# PULSE.net
KiCad netlist of a schematic drawn in Altium Designer
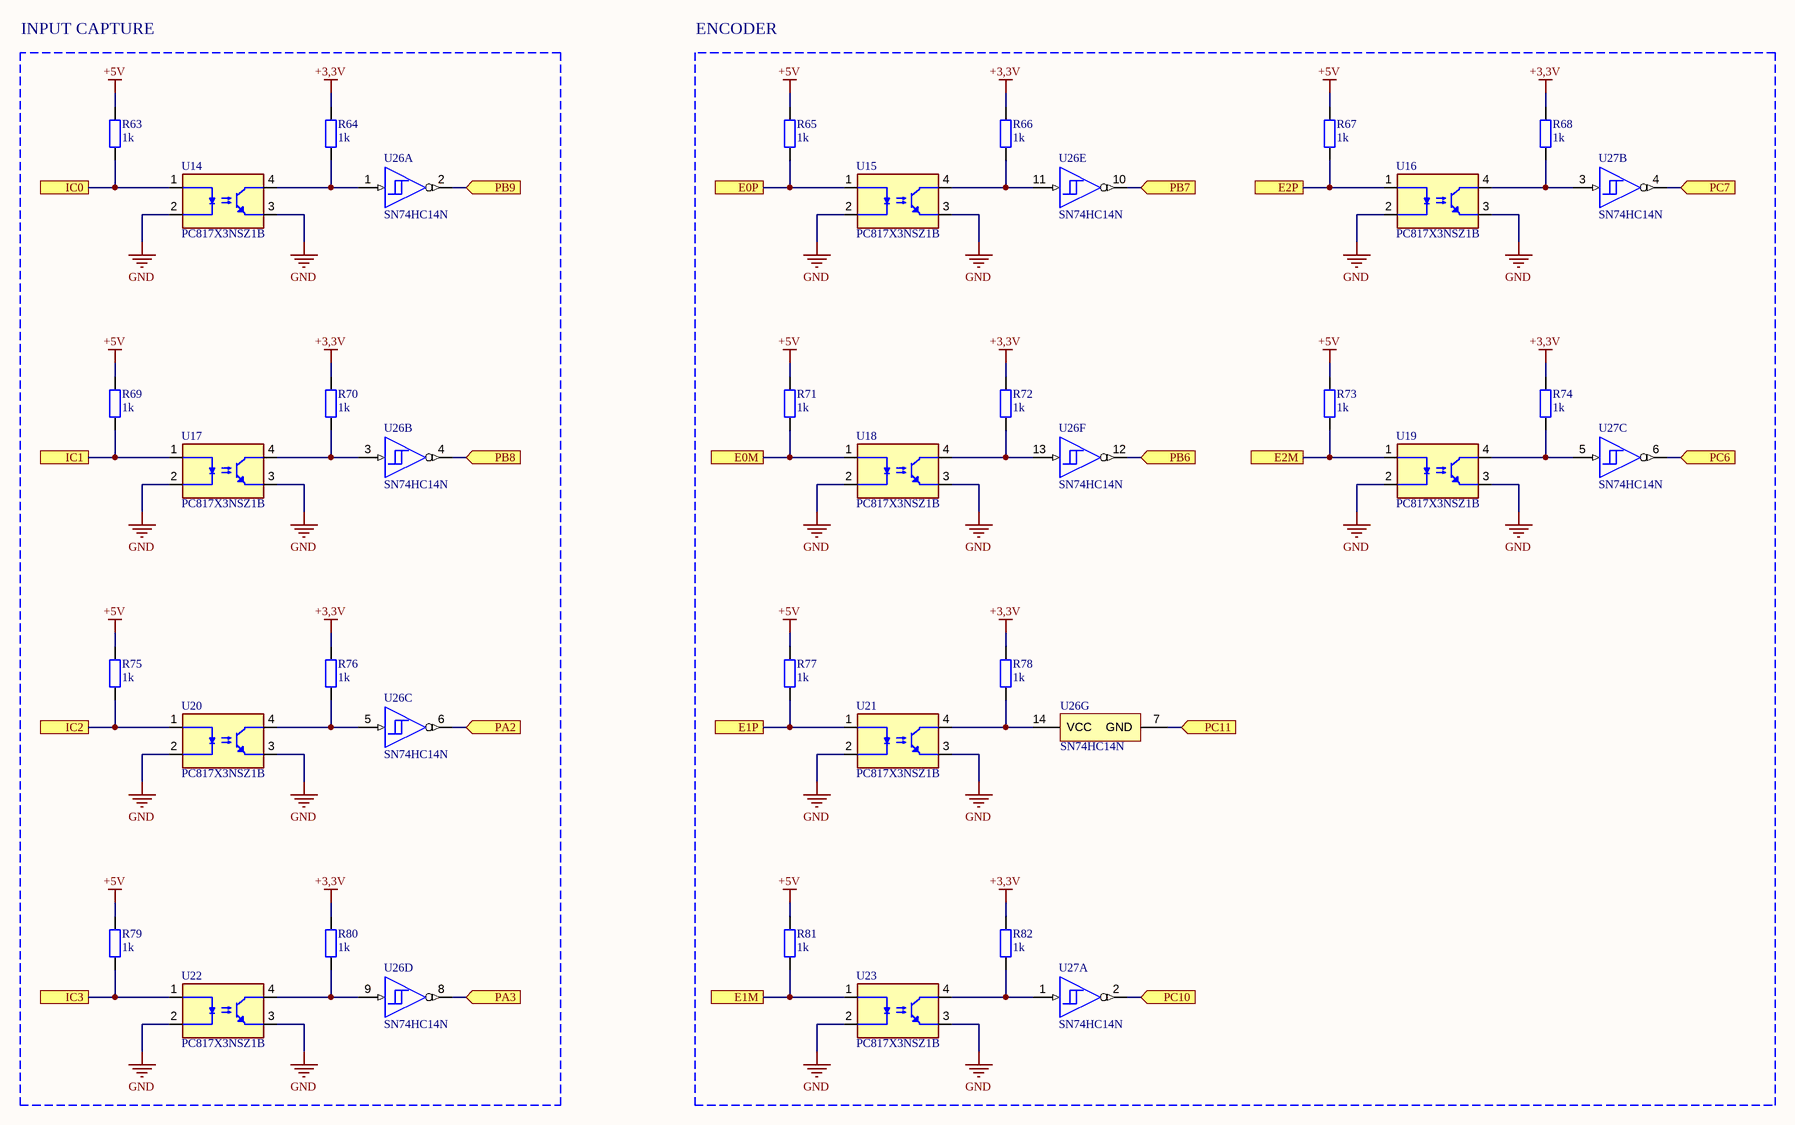
[diagram p0: PULSE.SchDoc]

(export (version "E")
  (design (tool "Eeschema 10.0.6"))
  (components
    (comp (ref "R63")
      (value "1k")
      (footprint "tro smd 0603")
      (description "RES")
      (libsource (lib "AUSB") (part "Tro 0603 1% 10k"))
    )
    (comp (ref "R64")
      (value "1k")
      (footprint "tro smd 0603")
      (description "RES")
      (libsource (lib "AUSB") (part "Tro 0603 1% 10k"))
    )
    (comp (ref "R65")
      (value "1k")
      (footprint "tro smd 0603")
      (description "RES")
      (libsource (lib "AUSB") (part "Tro 0603 1% 10k"))
    )
    (comp (ref "R66")
      (value "1k")
      (footprint "tro smd 0603")
      (description "RES")
      (libsource (lib "AUSB") (part "Tro 0603 1% 10k"))
    )
    (comp (ref "R67")
      (value "1k")
      (footprint "tro smd 0603")
      (description "RES")
      (libsource (lib "AUSB") (part "Tro 0603 1% 10k"))
    )
    (comp (ref "R68")
      (value "1k")
      (footprint "tro smd 0603")
      (description "RES")
      (libsource (lib "AUSB") (part "Tro 0603 1% 10k"))
    )
    (comp (ref "R69")
      (value "1k")
      (footprint "tro smd 0603")
      (description "RES")
      (libsource (lib "AUSB") (part "Tro 0603 1% 10k"))
    )
    (comp (ref "R70")
      (value "1k")
      (footprint "tro smd 0603")
      (description "RES")
      (libsource (lib "AUSB") (part "Tro 0603 1% 10k"))
    )
    (comp (ref "R71")
      (value "1k")
      (footprint "tro smd 0603")
      (description "RES")
      (libsource (lib "AUSB") (part "Tro 0603 1% 10k"))
    )
    (comp (ref "R72")
      (value "1k")
      (footprint "tro smd 0603")
      (description "RES")
      (libsource (lib "AUSB") (part "Tro 0603 1% 10k"))
    )
    (comp (ref "R73")
      (value "1k")
      (footprint "tro smd 0603")
      (description "RES")
      (libsource (lib "AUSB") (part "Tro 0603 1% 10k"))
    )
    (comp (ref "R74")
      (value "1k")
      (footprint "tro smd 0603")
      (description "RES")
      (libsource (lib "AUSB") (part "Tro 0603 1% 10k"))
    )
    (comp (ref "R75")
      (value "1k")
      (footprint "tro smd 0603")
      (description "RES")
      (libsource (lib "AUSB") (part "Tro 0603 1% 10k"))
    )
    (comp (ref "R76")
      (value "1k")
      (footprint "tro smd 0603")
      (description "RES")
      (libsource (lib "AUSB") (part "Tro 0603 1% 10k"))
    )
    (comp (ref "R77")
      (value "1k")
      (footprint "tro smd 0603")
      (description "RES")
      (libsource (lib "AUSB") (part "Tro 0603 1% 10k"))
    )
    (comp (ref "R78")
      (value "1k")
      (footprint "tro smd 0603")
      (description "RES")
      (libsource (lib "AUSB") (part "Tro 0603 1% 10k"))
    )
    (comp (ref "R79")
      (value "1k")
      (footprint "tro smd 0603")
      (description "RES")
      (libsource (lib "AUSB") (part "Tro 0603 1% 10k"))
    )
    (comp (ref "R80")
      (value "1k")
      (footprint "tro smd 0603")
      (description "RES")
      (libsource (lib "AUSB") (part "Tro 0603 1% 10k"))
    )
    (comp (ref "R81")
      (value "1k")
      (footprint "tro smd 0603")
      (description "RES")
      (libsource (lib "AUSB") (part "Tro 0603 1% 10k"))
    )
    (comp (ref "R82")
      (value "1k")
      (footprint "tro smd 0603")
      (description "RES")
      (libsource (lib "AUSB") (part "Tro 0603 1% 10k"))
    )
    (comp (ref "U14")
      (value "PC817X3NSZ1B")
      (footprint "DIP762W50P254L495H455Q4")
      (description "Optoisolator Transistor Output - 1 Channel 4-DIP")
      (fields (field (name "MF") "Sharp Microelectronics"))
      (libsource (lib "PC817X3NSZ1B") (part "PC817X3NSZ1B"))
    )
    (comp (ref "U15")
      (value "PC817X3NSZ1B")
      (footprint "DIP762W50P254L495H455Q4")
      (description "Optoisolator Transistor Output - 1 Channel 4-DIP")
      (fields (field (name "MF") "Sharp Microelectronics"))
      (libsource (lib "PC817X3NSZ1B") (part "PC817X3NSZ1B"))
    )
    (comp (ref "U16")
      (value "PC817X3NSZ1B")
      (footprint "DIP762W50P254L495H455Q4")
      (description "Optoisolator Transistor Output - 1 Channel 4-DIP")
      (fields (field (name "MF") "Sharp Microelectronics"))
      (libsource (lib "PC817X3NSZ1B") (part "PC817X3NSZ1B"))
    )
    (comp (ref "U17")
      (value "PC817X3NSZ1B")
      (footprint "DIP762W50P254L495H455Q4")
      (description "Optoisolator Transistor Output - 1 Channel 4-DIP")
      (fields (field (name "MF") "Sharp Microelectronics"))
      (libsource (lib "PC817X3NSZ1B") (part "PC817X3NSZ1B"))
    )
    (comp (ref "U18")
      (value "PC817X3NSZ1B")
      (footprint "DIP762W50P254L495H455Q4")
      (description "Optoisolator Transistor Output - 1 Channel 4-DIP")
      (fields (field (name "MF") "Sharp Microelectronics"))
      (libsource (lib "PC817X3NSZ1B") (part "PC817X3NSZ1B"))
    )
    (comp (ref "U19")
      (value "PC817X3NSZ1B")
      (footprint "DIP762W50P254L495H455Q4")
      (description "Optoisolator Transistor Output - 1 Channel 4-DIP")
      (fields (field (name "MF") "Sharp Microelectronics"))
      (libsource (lib "PC817X3NSZ1B") (part "PC817X3NSZ1B"))
    )
    (comp (ref "U20")
      (value "PC817X3NSZ1B")
      (footprint "DIP762W50P254L495H455Q4")
      (description "Optoisolator Transistor Output - 1 Channel 4-DIP")
      (fields (field (name "MF") "Sharp Microelectronics"))
      (libsource (lib "PC817X3NSZ1B") (part "PC817X3NSZ1B"))
    )
    (comp (ref "U21")
      (value "PC817X3NSZ1B")
      (footprint "DIP762W50P254L495H455Q4")
      (description "Optoisolator Transistor Output - 1 Channel 4-DIP")
      (fields (field (name "MF") "Sharp Microelectronics"))
      (libsource (lib "PC817X3NSZ1B") (part "PC817X3NSZ1B"))
    )
    (comp (ref "U22")
      (value "PC817X3NSZ1B")
      (footprint "DIP762W50P254L495H455Q4")
      (description "Optoisolator Transistor Output - 1 Channel 4-DIP")
      (fields (field (name "MF") "Sharp Microelectronics"))
      (libsource (lib "PC817X3NSZ1B") (part "PC817X3NSZ1B"))
    )
    (comp (ref "U23")
      (value "PC817X3NSZ1B")
      (footprint "DIP762W50P254L495H455Q4")
      (description "Optoisolator Transistor Output - 1 Channel 4-DIP")
      (fields (field (name "MF") "Sharp Microelectronics"))
      (libsource (lib "PC817X3NSZ1B") (part "PC817X3NSZ1B"))
    )
    (comp (ref "U26")
      (value "SN74HC14N")
      (footprint "N0014A")
      (description "Hex Schmitt-Trigger Inverters, N0014A, TUBE")
      (fields
        (field (name "MANUFACTURER") "Texas Instruments")
        (field (name "GENERIC PART NUMBER") "SN74HC14")
      )
      (libsource (lib "SN74HC14N") (part "CMP-1615-00889-3"))
    )
    (comp (ref "U27")
      (value "SN74HC14N")
      (footprint "N0014A")
      (description "Hex Schmitt-Trigger Inverters, N0014A, TUBE")
      (fields
        (field (name "MANUFACTURER") "Texas Instruments")
        (field (name "GENERIC PART NUMBER") "SN74HC14")
      )
      (libsource (lib "SN74HC14N") (part "CMP-1615-00889-3"))
    )
  )
  (nets
    (net (code "1") (name "+3,3V") (class "Default")
      (node (ref "R64") (pin "2") (pinfunction "2_2") (pintype "passive"))
      (node (ref "R66") (pin "2") (pinfunction "2_2") (pintype "passive"))
      (node (ref "R68") (pin "2") (pinfunction "2_2") (pintype "passive"))
      (node (ref "R70") (pin "2") (pinfunction "2_2") (pintype "passive"))
      (node (ref "R72") (pin "2") (pinfunction "2_2") (pintype "passive"))
      (node (ref "R74") (pin "2") (pinfunction "2_2") (pintype "passive"))
      (node (ref "R76") (pin "2") (pinfunction "2_2") (pintype "passive"))
      (node (ref "R78") (pin "2") (pinfunction "2_2") (pintype "passive"))
      (node (ref "R80") (pin "2") (pinfunction "2_2") (pintype "passive"))
      (node (ref "R82") (pin "2") (pinfunction "2_2") (pintype "passive"))
    )
    (net (code "2") (name "+5V") (class "Default")
      (node (ref "R63") (pin "2") (pinfunction "2_2") (pintype "passive"))
      (node (ref "R65") (pin "2") (pinfunction "2_2") (pintype "passive"))
      (node (ref "R67") (pin "2") (pinfunction "2_2") (pintype "passive"))
      (node (ref "R69") (pin "2") (pinfunction "2_2") (pintype "passive"))
      (node (ref "R71") (pin "2") (pinfunction "2_2") (pintype "passive"))
      (node (ref "R73") (pin "2") (pinfunction "2_2") (pintype "passive"))
      (node (ref "R75") (pin "2") (pinfunction "2_2") (pintype "passive"))
      (node (ref "R77") (pin "2") (pinfunction "2_2") (pintype "passive"))
      (node (ref "R79") (pin "2") (pinfunction "2_2") (pintype "passive"))
      (node (ref "R81") (pin "2") (pinfunction "2_2") (pintype "passive"))
    )
    (net (code "3") (name "/E0M") (class "Default")
      (node (ref "R71") (pin "1") (pinfunction "1_1") (pintype "passive"))
      (node (ref "U18") (pin "1") (pinfunction "ANODE_1") (pintype "passive"))
    )
    (net (code "4") (name "/E0P") (class "Default")
      (node (ref "R65") (pin "1") (pinfunction "1_1") (pintype "passive"))
      (node (ref "U15") (pin "1") (pinfunction "ANODE_1") (pintype "passive"))
    )
    (net (code "5") (name "/E1M") (class "Default")
      (node (ref "R81") (pin "1") (pinfunction "1_1") (pintype "passive"))
      (node (ref "U23") (pin "1") (pinfunction "ANODE_1") (pintype "passive"))
    )
    (net (code "6") (name "/E1P") (class "Default")
      (node (ref "R77") (pin "1") (pinfunction "1_1") (pintype "passive"))
      (node (ref "U21") (pin "1") (pinfunction "ANODE_1") (pintype "passive"))
    )
    (net (code "7") (name "/E2M") (class "Default")
      (node (ref "R73") (pin "1") (pinfunction "1_1") (pintype "passive"))
      (node (ref "U19") (pin "1") (pinfunction "ANODE_1") (pintype "passive"))
    )
    (net (code "8") (name "/E2P") (class "Default")
      (node (ref "R67") (pin "1") (pinfunction "1_1") (pintype "passive"))
      (node (ref "U16") (pin "1") (pinfunction "ANODE_1") (pintype "passive"))
    )
    (net (code "9") (name "/IC0") (class "Default")
      (node (ref "R63") (pin "1") (pinfunction "1_1") (pintype "passive"))
      (node (ref "U14") (pin "1") (pinfunction "ANODE_1") (pintype "passive"))
    )
    (net (code "10") (name "/IC1") (class "Default")
      (node (ref "R69") (pin "1") (pinfunction "1_1") (pintype "passive"))
      (node (ref "U17") (pin "1") (pinfunction "ANODE_1") (pintype "passive"))
    )
    (net (code "11") (name "/IC2") (class "Default")
      (node (ref "R75") (pin "1") (pinfunction "1_1") (pintype "passive"))
      (node (ref "U20") (pin "1") (pinfunction "ANODE_1") (pintype "passive"))
    )
    (net (code "12") (name "/IC3") (class "Default")
      (node (ref "R79") (pin "1") (pinfunction "1_1") (pintype "passive"))
      (node (ref "U22") (pin "1") (pinfunction "ANODE_1") (pintype "passive"))
    )
    (net (code "13") (name "/PA2") (class "Default")
      (node (ref "U26") (pin "6") (pinfunction "~{3Y}_6") (pintype "output"))
    )
    (net (code "14") (name "/PA3") (class "Default")
      (node (ref "U26") (pin "8") (pinfunction "~{4Y}_8") (pintype "output"))
    )
    (net (code "15") (name "/PB6") (class "Default")
      (node (ref "U26") (pin "12") (pinfunction "~{6Y}_12") (pintype "output"))
    )
    (net (code "16") (name "/PB7") (class "Default")
      (node (ref "U26") (pin "10") (pinfunction "~{5Y}_10") (pintype "output"))
    )
    (net (code "17") (name "/PB8") (class "Default")
      (node (ref "U26") (pin "4") (pinfunction "~{2Y}_4") (pintype "output"))
    )
    (net (code "18") (name "/PB9") (class "Default")
      (node (ref "U26") (pin "2") (pinfunction "~{1Y}_2") (pintype "output"))
    )
    (net (code "19") (name "/PC6") (class "Default")
      (node (ref "U27") (pin "6") (pinfunction "~{3Y}_6") (pintype "output"))
    )
    (net (code "20") (name "/PC7") (class "Default")
      (node (ref "U27") (pin "4") (pinfunction "~{2Y}_4") (pintype "output"))
    )
    (net (code "21") (name "/PC10") (class "Default")
      (node (ref "U27") (pin "2") (pinfunction "~{1Y}_2") (pintype "output"))
    )
    (net (code "22") (name "/PC11") (class "Default")
      (node (ref "U26") (pin "7") (pinfunction "GND_7") (pintype "power_in"))
    )
    (net (code "23") (name "GND") (class "Default")
      (node (ref "U14") (pin "2") (pinfunction "CATHODE_2") (pintype "passive"))
      (node (ref "U14") (pin "3") (pinfunction "EMITTER_3") (pintype "passive"))
      (node (ref "U15") (pin "2") (pinfunction "CATHODE_2") (pintype "passive"))
      (node (ref "U15") (pin "3") (pinfunction "EMITTER_3") (pintype "passive"))
      (node (ref "U16") (pin "2") (pinfunction "CATHODE_2") (pintype "passive"))
      (node (ref "U16") (pin "3") (pinfunction "EMITTER_3") (pintype "passive"))
      (node (ref "U17") (pin "2") (pinfunction "CATHODE_2") (pintype "passive"))
      (node (ref "U17") (pin "3") (pinfunction "EMITTER_3") (pintype "passive"))
      (node (ref "U18") (pin "2") (pinfunction "CATHODE_2") (pintype "passive"))
      (node (ref "U18") (pin "3") (pinfunction "EMITTER_3") (pintype "passive"))
      (node (ref "U19") (pin "2") (pinfunction "CATHODE_2") (pintype "passive"))
      (node (ref "U19") (pin "3") (pinfunction "EMITTER_3") (pintype "passive"))
      (node (ref "U20") (pin "2") (pinfunction "CATHODE_2") (pintype "passive"))
      (node (ref "U20") (pin "3") (pinfunction "EMITTER_3") (pintype "passive"))
      (node (ref "U21") (pin "2") (pinfunction "CATHODE_2") (pintype "passive"))
      (node (ref "U21") (pin "3") (pinfunction "EMITTER_3") (pintype "passive"))
      (node (ref "U22") (pin "2") (pinfunction "CATHODE_2") (pintype "passive"))
      (node (ref "U22") (pin "3") (pinfunction "EMITTER_3") (pintype "passive"))
      (node (ref "U23") (pin "2") (pinfunction "CATHODE_2") (pintype "passive"))
      (node (ref "U23") (pin "3") (pinfunction "EMITTER_3") (pintype "passive"))
    )
    (net (code "24") (name "Net-(U14-COLLECTOR)") (class "Default")
      (node (ref "R64") (pin "1") (pinfunction "1_1") (pintype "passive"))
      (node (ref "U14") (pin "4") (pinfunction "COLLECTOR_4") (pintype "passive"))
      (node (ref "U26") (pin "1") (pinfunction "1A_1") (pintype "input"))
    )
    (net (code "25") (name "Net-(U15-COLLECTOR)") (class "Default")
      (node (ref "R66") (pin "1") (pinfunction "1_1") (pintype "passive"))
      (node (ref "U15") (pin "4") (pinfunction "COLLECTOR_4") (pintype "passive"))
      (node (ref "U26") (pin "11") (pinfunction "5A_11") (pintype "input"))
    )
    (net (code "26") (name "Net-(U16-COLLECTOR)") (class "Default")
      (node (ref "R68") (pin "1") (pinfunction "1_1") (pintype "passive"))
      (node (ref "U16") (pin "4") (pinfunction "COLLECTOR_4") (pintype "passive"))
      (node (ref "U27") (pin "3") (pinfunction "2A_3") (pintype "input"))
    )
    (net (code "27") (name "Net-(U17-COLLECTOR)") (class "Default")
      (node (ref "R70") (pin "1") (pinfunction "1_1") (pintype "passive"))
      (node (ref "U17") (pin "4") (pinfunction "COLLECTOR_4") (pintype "passive"))
      (node (ref "U26") (pin "3") (pinfunction "2A_3") (pintype "input"))
    )
    (net (code "28") (name "Net-(U18-COLLECTOR)") (class "Default")
      (node (ref "R72") (pin "1") (pinfunction "1_1") (pintype "passive"))
      (node (ref "U18") (pin "4") (pinfunction "COLLECTOR_4") (pintype "passive"))
      (node (ref "U26") (pin "13") (pinfunction "6A_13") (pintype "input"))
    )
    (net (code "29") (name "Net-(U19-COLLECTOR)") (class "Default")
      (node (ref "R74") (pin "1") (pinfunction "1_1") (pintype "passive"))
      (node (ref "U19") (pin "4") (pinfunction "COLLECTOR_4") (pintype "passive"))
      (node (ref "U27") (pin "5") (pinfunction "3A_5") (pintype "input"))
    )
    (net (code "30") (name "Net-(U20-COLLECTOR)") (class "Default")
      (node (ref "R76") (pin "1") (pinfunction "1_1") (pintype "passive"))
      (node (ref "U20") (pin "4") (pinfunction "COLLECTOR_4") (pintype "passive"))
      (node (ref "U26") (pin "5") (pinfunction "3A_5") (pintype "input"))
    )
    (net (code "31") (name "Net-(U21-COLLECTOR)") (class "Default")
      (node (ref "R78") (pin "1") (pinfunction "1_1") (pintype "passive"))
      (node (ref "U21") (pin "4") (pinfunction "COLLECTOR_4") (pintype "passive"))
      (node (ref "U26") (pin "14") (pinfunction "VCC_14") (pintype "power_in"))
    )
    (net (code "32") (name "Net-(U22-COLLECTOR)") (class "Default")
      (node (ref "R80") (pin "1") (pinfunction "1_1") (pintype "passive"))
      (node (ref "U22") (pin "4") (pinfunction "COLLECTOR_4") (pintype "passive"))
      (node (ref "U26") (pin "9") (pinfunction "4A_9") (pintype "input"))
    )
    (net (code "33") (name "Net-(U23-COLLECTOR)") (class "Default")
      (node (ref "R82") (pin "1") (pinfunction "1_1") (pintype "passive"))
      (node (ref "U23") (pin "4") (pinfunction "COLLECTOR_4") (pintype "passive"))
      (node (ref "U27") (pin "1") (pinfunction "1A_1") (pintype "input"))
    )
  )
)
